# ESP8266_1wire_Gateway_NodeMCU_WeMosD1Min.net
KiCad netlist of a schematic drawn in EAGLE
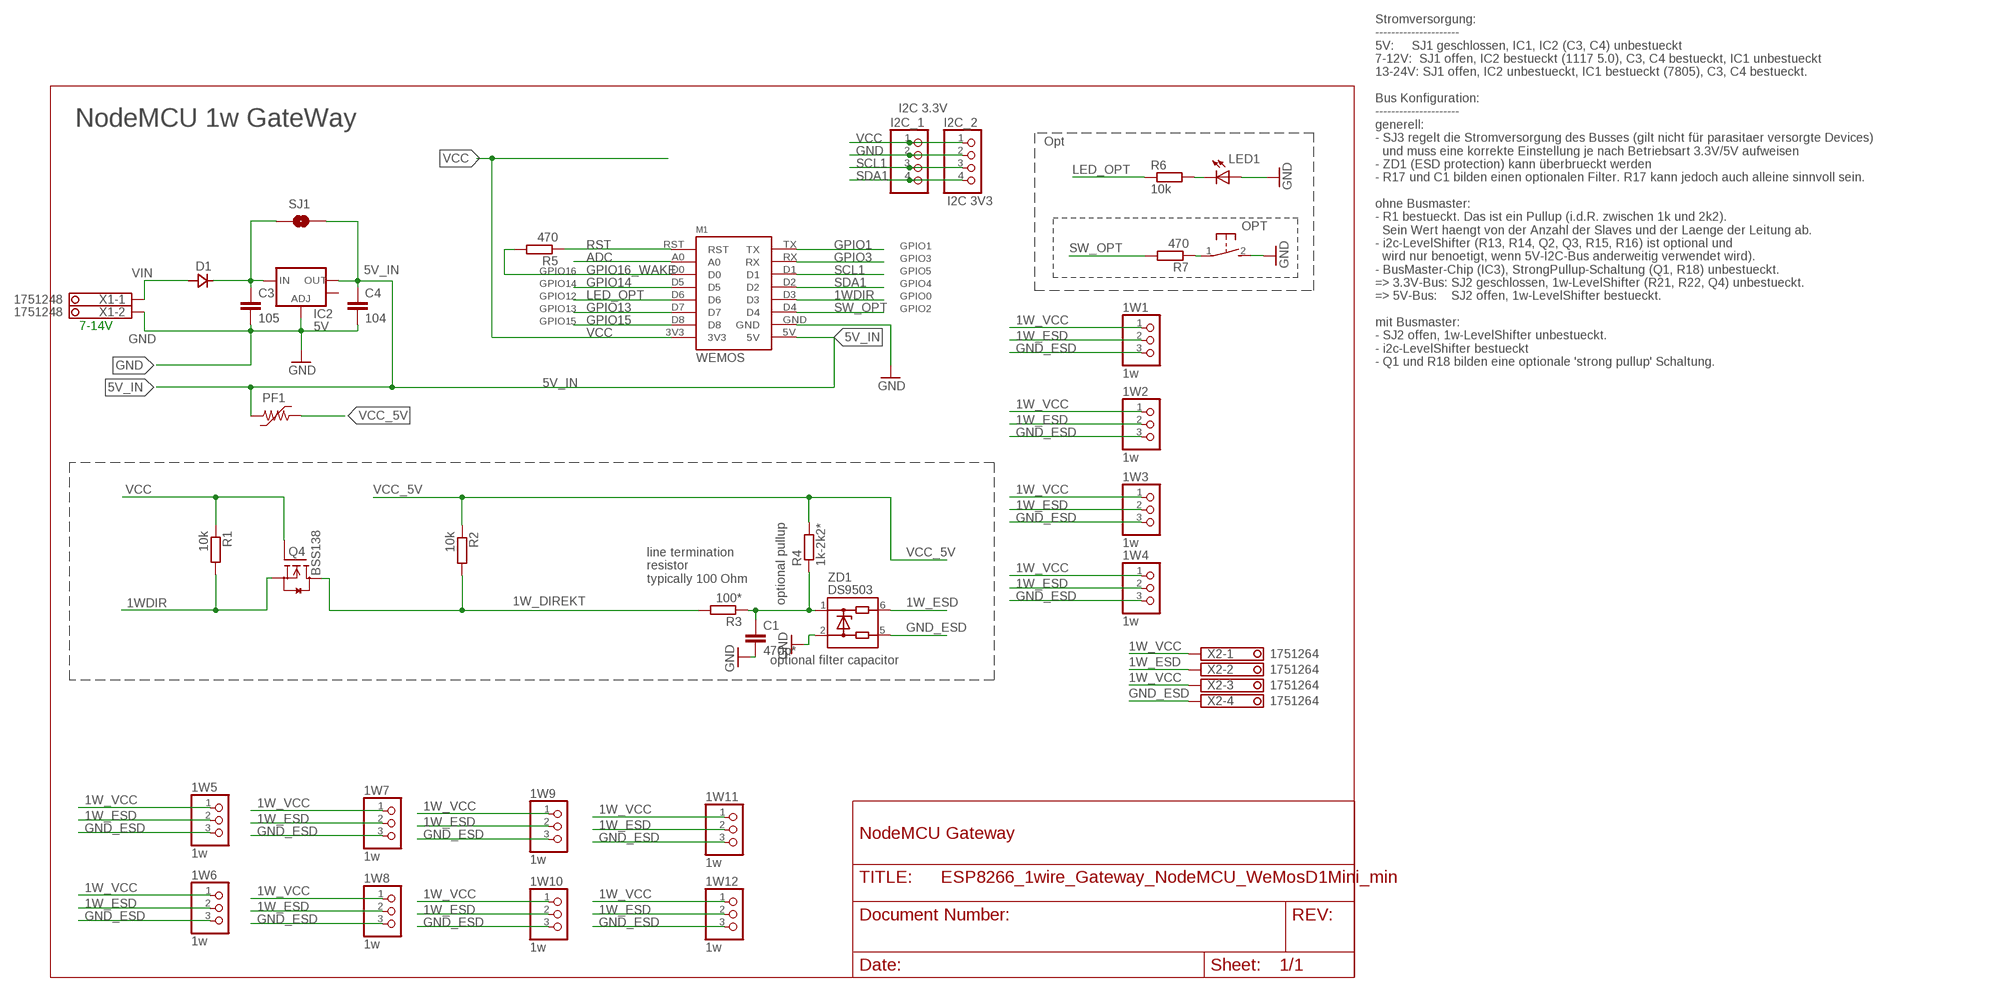
[diagram p0: schematic, sheet 1]

(export (version "E")
  (design (tool "Eeschema 10.0.6"))
  (components
    (comp (ref "1W1")
      (value "1w")
      (footprint "eagle-import:1X03")
      (libsource (lib "eagle-import") (part "PINHD-1X3_S"))
    )
    (comp (ref "1W2")
      (value "1w")
      (footprint "eagle-import:1X03")
      (libsource (lib "eagle-import") (part "PINHD-1X3_S"))
    )
    (comp (ref "1W3")
      (value "1w")
      (footprint "eagle-import:1X03")
      (libsource (lib "eagle-import") (part "PINHD-1X3_S"))
    )
    (comp (ref "1W4")
      (value "1w")
      (footprint "eagle-import:1X03")
      (libsource (lib "eagle-import") (part "PINHD-1X3_S"))
    )
    (comp (ref "1W5")
      (value "1w")
      (footprint "eagle-import:1X03")
      (libsource (lib "eagle-import") (part "PINHD-1X3_S"))
    )
    (comp (ref "1W6")
      (value "1w")
      (footprint "eagle-import:1X03")
      (libsource (lib "eagle-import") (part "PINHD-1X3_S"))
    )
    (comp (ref "1W7")
      (value "1w")
      (footprint "eagle-import:1X03")
      (libsource (lib "eagle-import") (part "PINHD-1X3_S"))
    )
    (comp (ref "1W8")
      (value "1w")
      (footprint "eagle-import:1X03")
      (libsource (lib "eagle-import") (part "PINHD-1X3_S"))
    )
    (comp (ref "1W9")
      (value "1w")
      (footprint "eagle-import:1X03")
      (libsource (lib "eagle-import") (part "PINHD-1X3_S"))
    )
    (comp (ref "1W10")
      (value "1w")
      (footprint "eagle-import:1X03")
      (libsource (lib "eagle-import") (part "PINHD-1X3_S"))
    )
    (comp (ref "1W11")
      (value "1w")
      (footprint "eagle-import:1X03")
      (libsource (lib "eagle-import") (part "PINHD-1X3_S"))
    )
    (comp (ref "1W12")
      (value "1w")
      (footprint "eagle-import:1X03")
      (libsource (lib "eagle-import") (part "PINHD-1X3_S"))
    )
    (comp (ref "C1")
      (value "470p*")
      (footprint "eagle-import:C0805")
      (libsource (lib "eagle-import") (part "C-EUC0805"))
    )
    (comp (ref "C3")
      (value "105")
      (footprint "eagle-import:C0805")
      (libsource (lib "eagle-import") (part "C-EUC0805"))
    )
    (comp (ref "C4")
      (value "104")
      (footprint "eagle-import:C0805")
      (libsource (lib "eagle-import") (part "C-EUC0805"))
    )
    (comp (ref "D1")
      (value "SS14")
      (footprint "eagle-import:DO214")
      (libsource (lib "eagle-import") (part "SS14"))
    )
    (comp (ref "I2C_1")
      (value "PINHD-1X4_S")
      (footprint "eagle-import:1X04")
      (libsource (lib "eagle-import") (part "PINHD-1X4_S"))
    )
    (comp (ref "I2C_2")
      (value "I2C 3V3")
      (footprint "eagle-import:1X04")
      (libsource (lib "eagle-import") (part "PINHD-1X4_S"))
    )
    (comp (ref "IC2")
      (value "5V")
      (footprint "eagle-import:SOT223")
      (libsource (lib "eagle-import") (part "V_REG_LM1117SOT223"))
    )
    (comp (ref "LED1")
      (value "CFG")
      (footprint "eagle-import:CHIPLED_1206")
      (libsource (lib "eagle-import") (part "LEDCHIPLED_1206"))
    )
    (comp (ref "M1")
      (value "WEMOS")
      (footprint "eagle-import:WEMOS")
      (libsource (lib "eagle-import") (part "WEMOS"))
    )
    (comp (ref "OPT")
      (value "OPT")
      (footprint "eagle-import:DTSM-3")
      (libsource (lib "eagle-import") (part "DTSM-3"))
    )
    (comp (ref "PF1")
      (value "500mA")
      (footprint "eagle-import:F1206")
      (libsource (lib "eagle-import") (part "PTC-F1206"))
    )
    (comp (ref "Q4")
      (value "BSS138")
      (footprint "eagle-import:SOT23")
      (libsource (lib "eagle-import") (part "BSS138"))
    )
    (comp (ref "R1")
      (value "10k")
      (footprint "eagle-import:R0805")
      (libsource (lib "eagle-import") (part "resistor_R-EU_R0805"))
    )
    (comp (ref "R2")
      (value "10k")
      (footprint "eagle-import:R0805")
      (libsource (lib "eagle-import") (part "resistor_R-EU_R0805"))
    )
    (comp (ref "R3")
      (value "100*")
      (footprint "eagle-import:R0805_SMALL_GAP")
      (libsource (lib "eagle-import") (part "R0805_SMALL_GAP"))
    )
    (comp (ref "R4")
      (value "1k-2k2*")
      (footprint "eagle-import:R0805")
      (libsource (lib "eagle-import") (part "R-EU_R0805"))
    )
    (comp (ref "R5")
      (value "470")
      (footprint "eagle-import:R0805")
      (libsource (lib "eagle-import") (part "resistor_R-EU_R0805"))
    )
    (comp (ref "R6")
      (value "10k")
      (footprint "eagle-import:R0805")
      (libsource (lib "eagle-import") (part "R-EU_R0805"))
    )
    (comp (ref "R7")
      (value "470")
      (footprint "eagle-import:R0805")
      (libsource (lib "eagle-import") (part "resistor_R-EU_R0805"))
    )
    (comp (ref "SJ1")
      (value "bypass vreg")
      (footprint "eagle-import:PAD-JUMPER-2-NO_YES_SILK")
      (libsource (lib "eagle-import") (part "JUMPER-PAD-2-NOYES_SILK"))
    )
    (comp (ref "X1")
      (value "1751248")
      (footprint "eagle-import:1751248")
      (libsource (lib "eagle-import") (part "1751248"))
    )
    (comp (ref "X2")
      (value "1751264")
      (footprint "eagle-import:1751264")
      (libsource (lib "eagle-import") (part "1751264"))
    )
    (comp (ref "ZD1")
      (value "DS9503")
      (footprint "eagle-import:TSOC6_BYPASS_J")
      (libsource (lib "eagle-import") (part "DS9503_BYPASS_JP"))
    )
  )
  (nets
    (net (code "1") (name "/1WDIR") (class "Default")
      (node (ref "M1") (pin "D3") (pinfunction "D3_D3") (pintype "bidirectional"))
      (node (ref "Q4") (pin "2") (pinfunction "S_2") (pintype "passive"))
      (node (ref "R1") (pin "2") (pinfunction "2_2") (pintype "passive"))
    )
    (net (code "2") (name "/1W_DIREKT") (class "Default")
      (node (ref "Q4") (pin "3") (pinfunction "D_3") (pintype "passive"))
      (node (ref "R2") (pin "2") (pinfunction "2_2") (pintype "passive"))
      (node (ref "R3") (pin "2") (pinfunction "2_2") (pintype "passive"))
    )
    (net (code "3") (name "/1W_ESD") (class "Default")
      (node (ref "1W1") (pin "2") (pinfunction "2_2") (pintype "passive"))
      (node (ref "1W10") (pin "2") (pinfunction "2_2") (pintype "passive"))
      (node (ref "1W11") (pin "2") (pinfunction "2_2") (pintype "passive"))
      (node (ref "1W12") (pin "2") (pinfunction "2_2") (pintype "passive"))
      (node (ref "1W2") (pin "2") (pinfunction "2_2") (pintype "passive"))
      (node (ref "1W3") (pin "2") (pinfunction "2_2") (pintype "passive"))
      (node (ref "1W4") (pin "2") (pinfunction "2_2") (pintype "passive"))
      (node (ref "1W5") (pin "2") (pinfunction "2_2") (pintype "passive"))
      (node (ref "1W6") (pin "2") (pinfunction "2_2") (pintype "passive"))
      (node (ref "1W7") (pin "2") (pinfunction "2_2") (pintype "passive"))
      (node (ref "1W8") (pin "2") (pinfunction "2_2") (pintype "passive"))
      (node (ref "1W9") (pin "2") (pinfunction "2_2") (pintype "passive"))
      (node (ref "X2") (pin "2") (pinfunction "K_2") (pintype "passive"))
      (node (ref "ZD1") (pin "6") (pinfunction "P$4_6") (pintype "passive"))
    )
    (net (code "4") (name "/1W_VCC") (class "Default")
      (node (ref "1W1") (pin "1") (pinfunction "1_1") (pintype "passive"))
      (node (ref "1W10") (pin "1") (pinfunction "1_1") (pintype "passive"))
      (node (ref "1W11") (pin "1") (pinfunction "1_1") (pintype "passive"))
      (node (ref "1W12") (pin "1") (pinfunction "1_1") (pintype "passive"))
      (node (ref "1W2") (pin "1") (pinfunction "1_1") (pintype "passive"))
      (node (ref "1W3") (pin "1") (pinfunction "1_1") (pintype "passive"))
      (node (ref "1W4") (pin "1") (pinfunction "1_1") (pintype "passive"))
      (node (ref "1W5") (pin "1") (pinfunction "1_1") (pintype "passive"))
      (node (ref "1W6") (pin "1") (pinfunction "1_1") (pintype "passive"))
      (node (ref "1W7") (pin "1") (pinfunction "1_1") (pintype "passive"))
      (node (ref "1W8") (pin "1") (pinfunction "1_1") (pintype "passive"))
      (node (ref "1W9") (pin "1") (pinfunction "1_1") (pintype "passive"))
      (node (ref "X2") (pin "1") (pinfunction "K_1") (pintype "passive"))
      (node (ref "X2") (pin "3") (pinfunction "K_3") (pintype "passive"))
    )
    (net (code "5") (name "/ADC") (class "Default")
      (node (ref "M1") (pin "A0") (pinfunction "A0_A0") (pintype "bidirectional"))
    )
    (net (code "6") (name "/GND_ESD") (class "Default")
      (node (ref "1W1") (pin "3") (pinfunction "3_3") (pintype "passive"))
      (node (ref "1W10") (pin "3") (pinfunction "3_3") (pintype "passive"))
      (node (ref "1W11") (pin "3") (pinfunction "3_3") (pintype "passive"))
      (node (ref "1W12") (pin "3") (pinfunction "3_3") (pintype "passive"))
      (node (ref "1W2") (pin "3") (pinfunction "3_3") (pintype "passive"))
      (node (ref "1W3") (pin "3") (pinfunction "3_3") (pintype "passive"))
      (node (ref "1W4") (pin "3") (pinfunction "3_3") (pintype "passive"))
      (node (ref "1W5") (pin "3") (pinfunction "3_3") (pintype "passive"))
      (node (ref "1W6") (pin "3") (pinfunction "3_3") (pintype "passive"))
      (node (ref "1W7") (pin "3") (pinfunction "3_3") (pintype "passive"))
      (node (ref "1W8") (pin "3") (pinfunction "3_3") (pintype "passive"))
      (node (ref "1W9") (pin "3") (pinfunction "3_3") (pintype "passive"))
      (node (ref "X2") (pin "4") (pinfunction "K_4") (pintype "passive"))
      (node (ref "ZD1") (pin "5") (pinfunction "P$3_5") (pintype "passive"))
    )
    (net (code "7") (name "/GPIO1") (class "Default")
      (node (ref "M1") (pin "TX") (pinfunction "TX_TX") (pintype "bidirectional"))
    )
    (net (code "8") (name "/GPIO3") (class "Default")
      (node (ref "M1") (pin "RX") (pinfunction "RX_RX") (pintype "bidirectional"))
    )
    (net (code "9") (name "/GPIO13") (class "Default")
      (node (ref "M1") (pin "D7") (pinfunction "D7_D7") (pintype "bidirectional"))
    )
    (net (code "10") (name "/GPIO14") (class "Default")
      (node (ref "M1") (pin "D5") (pinfunction "D5_D5") (pintype "bidirectional"))
    )
    (net (code "11") (name "/GPIO15") (class "Default")
      (node (ref "M1") (pin "D8") (pinfunction "D8_D8") (pintype "bidirectional"))
    )
    (net (code "12") (name "/GPIO16_WAKE") (class "Default")
      (node (ref "M1") (pin "D0") (pinfunction "D0_D0") (pintype "bidirectional"))
      (node (ref "R5") (pin "2") (pinfunction "2_2") (pintype "passive"))
    )
    (net (code "13") (name "/LED_OPT") (class "Default")
      (node (ref "M1") (pin "D6") (pinfunction "D6_D6") (pintype "bidirectional"))
      (node (ref "R6") (pin "1") (pinfunction "1_1") (pintype "passive"))
    )
    (net (code "14") (name "/RST") (class "Default")
      (node (ref "M1") (pin "RST") (pinfunction "RST_RST") (pintype "bidirectional"))
      (node (ref "R5") (pin "1") (pinfunction "1_1") (pintype "passive"))
    )
    (net (code "15") (name "/SCL1") (class "Default")
      (node (ref "I2C_1") (pin "3") (pinfunction "3_3") (pintype "passive"))
      (node (ref "I2C_2") (pin "3") (pinfunction "3_3") (pintype "passive"))
      (node (ref "M1") (pin "D1") (pinfunction "D1_D1") (pintype "bidirectional"))
    )
    (net (code "16") (name "/SDA1") (class "Default")
      (node (ref "I2C_1") (pin "4") (pinfunction "4_4") (pintype "passive"))
      (node (ref "I2C_2") (pin "4") (pinfunction "4_4") (pintype "passive"))
      (node (ref "M1") (pin "D2") (pinfunction "D2_D2") (pintype "bidirectional"))
    )
    (net (code "17") (name "/SW_OPT") (class "Default")
      (node (ref "M1") (pin "D4") (pinfunction "D4_D4") (pintype "bidirectional"))
      (node (ref "R7") (pin "2") (pinfunction "2_2") (pintype "passive"))
    )
    (net (code "18") (name "/VIN") (class "Default")
      (node (ref "D1") (pin "ANODE") (pinfunction "ANODE_ANODE") (pintype "bidirectional"))
      (node (ref "X1") (pin "1") (pinfunction "K_1") (pintype "passive"))
    )
    (net (code "19") (name "5V_IN") (class "Default")
      (node (ref "C4") (pin "1") (pinfunction "1_1") (pintype "passive"))
      (node (ref "IC2") (pin "2") (pinfunction "OUT_2") (pintype "output"))
      (node (ref "M1") (pin "5V") (pinfunction "5V_5V") (pintype "bidirectional"))
      (node (ref "PF1") (pin "2") (pinfunction "2_2") (pintype "passive"))
      (node (ref "SJ1") (pin "2") (pinfunction "2_2") (pintype "passive"))
    )
    (net (code "20") (name "GND") (class "Default")
      (node (ref "C1") (pin "2") (pinfunction "2_2") (pintype "passive"))
      (node (ref "C3") (pin "2") (pinfunction "2_2") (pintype "passive"))
      (node (ref "C4") (pin "2") (pinfunction "2_2") (pintype "passive"))
      (node (ref "I2C_1") (pin "2") (pinfunction "2_2") (pintype "passive"))
      (node (ref "I2C_2") (pin "2") (pinfunction "2_2") (pintype "passive"))
      (node (ref "IC2") (pin "1") (pinfunction "ADJ_1") (pintype "input"))
      (node (ref "LED1") (pin "A") (pinfunction "A_A") (pintype "passive"))
      (node (ref "M1") (pin "GND") (pinfunction "GND_GND") (pintype "bidirectional"))
      (node (ref "OPT") (pin "2") (pinfunction "2_2") (pintype "passive"))
      (node (ref "X1") (pin "2") (pinfunction "K_2") (pintype "passive"))
      (node (ref "ZD1") (pin "2") (pinfunction "P$2_2") (pintype "passive"))
    )
    (net (code "21") (name "Net-(IC2-IN)") (class "Default")
      (node (ref "C3") (pin "1") (pinfunction "1_1") (pintype "passive"))
      (node (ref "D1") (pin "CATHODE") (pinfunction "CATHODE_CATHODE") (pintype "bidirectional"))
      (node (ref "IC2") (pin "3") (pinfunction "IN_3") (pintype "input"))
      (node (ref "SJ1") (pin "1") (pinfunction "1_1") (pintype "passive"))
    )
    (net (code "22") (name "Net-(LED1-PadC)") (class "Default")
      (node (ref "LED1") (pin "C") (pinfunction "C_C") (pintype "passive"))
      (node (ref "R6") (pin "2") (pinfunction "2_2") (pintype "passive"))
    )
    (net (code "23") (name "Net-(OPT-Pad1)") (class "Default")
      (node (ref "OPT") (pin "1") (pinfunction "1_1") (pintype "passive"))
      (node (ref "R7") (pin "1") (pinfunction "1_1") (pintype "passive"))
    )
    (net (code "24") (name "Net-(ZD1-P$1)") (class "Default")
      (node (ref "C1") (pin "1") (pinfunction "1_1") (pintype "passive"))
      (node (ref "R3") (pin "1") (pinfunction "1_1") (pintype "passive"))
      (node (ref "R4") (pin "1") (pinfunction "1_1") (pintype "passive"))
      (node (ref "ZD1") (pin "1") (pinfunction "P$1_1") (pintype "passive"))
    )
    (net (code "25") (name "VCC") (class "Default")
      (node (ref "I2C_1") (pin "1") (pinfunction "1_1") (pintype "passive"))
      (node (ref "I2C_2") (pin "1") (pinfunction "1_1") (pintype "passive"))
      (node (ref "M1") (pin "3V3") (pinfunction "3V3_3V3") (pintype "bidirectional"))
      (node (ref "Q4") (pin "1") (pinfunction "G_1") (pintype "passive"))
      (node (ref "R1") (pin "1") (pinfunction "1_1") (pintype "passive"))
    )
    (net (code "26") (name "VCC_5V") (class "Default")
      (node (ref "PF1") (pin "1") (pinfunction "1_1") (pintype "passive"))
      (node (ref "R2") (pin "1") (pinfunction "1_1") (pintype "passive"))
      (node (ref "R4") (pin "2") (pinfunction "2_2") (pintype "passive"))
    )
    (net (code "27") (name "unconnected-(IC2-OUT-Pad4)") (class "Default")
      (node (ref "IC2") (pin "4") (pinfunction "OUT_4") (pintype "output"))
    )
  )
)
